# Pulse_Earing_3.net
KiCad netlist of a schematic drawn in EAGLE
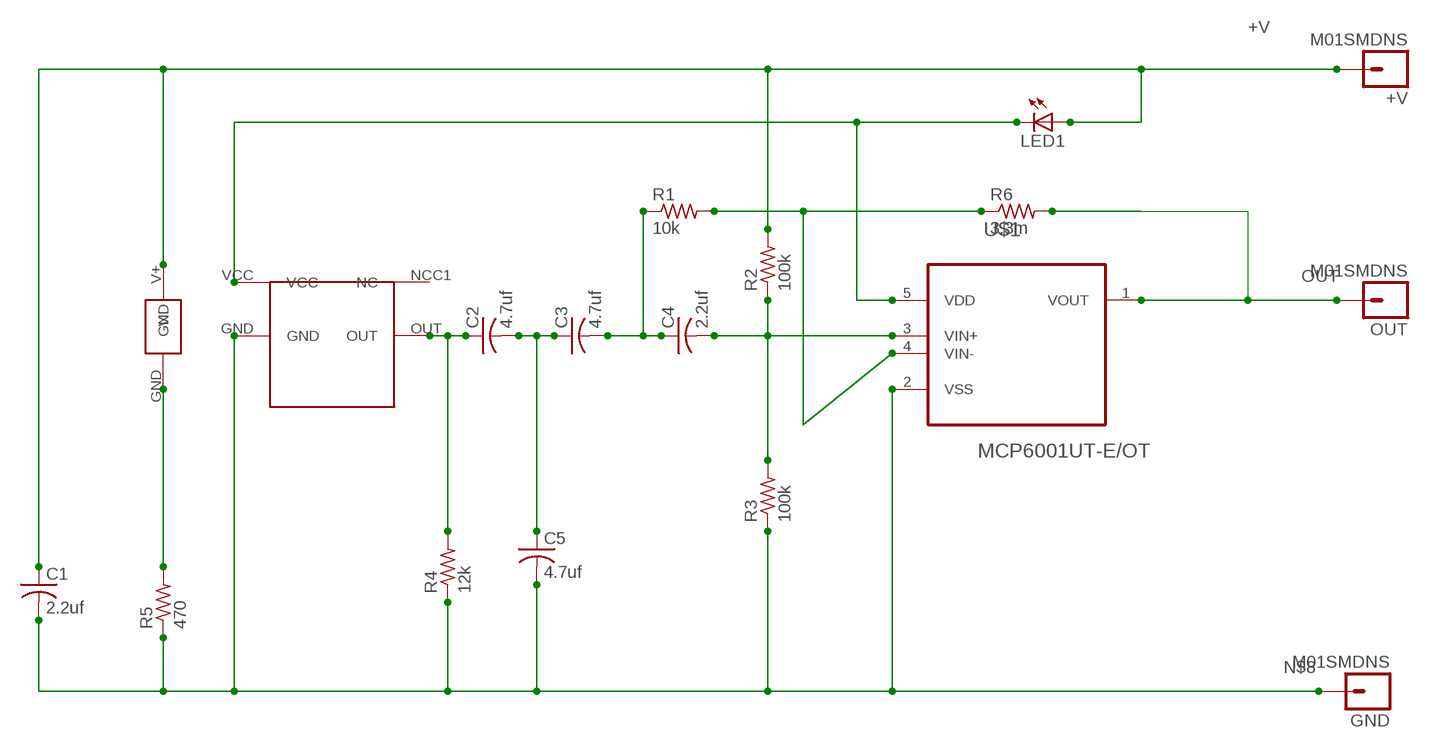
[diagram p0: schematic, sheet 1]

(export (version "E")
  (design (tool "Eeschema 10.0.6"))
  (components
    (comp (ref "+V")
      (value "M01SMDNS")
      (footprint "eagle-import:1X01NS")
      (libsource (lib "eagle-import") (part "M01SMDNS"))
    )
    (comp (ref "C1")
      (value "2.2uf")
      (footprint "eagle-import:C0402")
      (libsource (lib "eagle-import") (part "C-USC0402"))
    )
    (comp (ref "C2")
      (value "4.7uf")
      (footprint "eagle-import:C0402")
      (libsource (lib "eagle-import") (part "C-USC0402"))
    )
    (comp (ref "C3")
      (value "4.7uf")
      (footprint "eagle-import:C0402")
      (libsource (lib "eagle-import") (part "C-USC0402"))
    )
    (comp (ref "C4")
      (value "2.2uf")
      (footprint "eagle-import:C0402")
      (libsource (lib "eagle-import") (part "C-USC0402"))
    )
    (comp (ref "C5")
      (value "4.7uf")
      (footprint "eagle-import:C0402")
      (libsource (lib "eagle-import") (part "C-USC0402"))
    )
    (comp (ref "GND")
      (value "M01SMDNS")
      (footprint "eagle-import:1X01NS")
      (libsource (lib "eagle-import") (part "M01SMDNS"))
    )
    (comp (ref "LED1")
      (value "LEDCHIP-LED0603")
      (footprint "eagle-import:CHIP-LED0603")
      (libsource (lib "eagle-import") (part "LEDCHIP-LED0603"))
    )
    (comp (ref "OUT")
      (value "M01SMDNS")
      (footprint "eagle-import:1X01NS")
      (libsource (lib "eagle-import") (part "M01SMDNS"))
    )
    (comp (ref "R1")
      (value "10k")
      (footprint "eagle-import:R0402")
      (libsource (lib "eagle-import") (part "R-US_R0402"))
    )
    (comp (ref "R2")
      (value "100k")
      (footprint "eagle-import:R0402")
      (libsource (lib "eagle-import") (part "R-US_R0402"))
    )
    (comp (ref "R3")
      (value "100k")
      (footprint "eagle-import:R0402")
      (libsource (lib "eagle-import") (part "R-US_R0402"))
    )
    (comp (ref "R4")
      (value "12k")
      (footprint "eagle-import:R0402")
      (libsource (lib "eagle-import") (part "R-US_R0402"))
    )
    (comp (ref "R5")
      (value "470")
      (footprint "eagle-import:R0402")
      (libsource (lib "eagle-import") (part "R-US_R0402"))
    )
    (comp (ref "R6")
      (value "3.3m")
      (footprint "eagle-import:R0402")
      (libsource (lib "eagle-import") (part "R-US_R0402"))
    )
    (comp (ref "U$1")
      (value "MCP6001UT-E/OT")
      (footprint "eagle-import:SOT95P270X145-5N")
      (libsource (lib "eagle-import") (part "MCP6001UT-E/OT"))
    )
    (comp (ref "U$2")
      (value "APDS9008")
      (footprint "eagle-import:APDS9008")
      (libsource (lib "eagle-import") (part "APDS9008"))
    )
    (comp (ref "U$3")
      (value "KBREVMTNLED")
      (footprint "eagle-import:KBREVMNTLED")
      (libsource (lib "eagle-import") (part "KBREVMTNLED"))
    )
  )
  (nets
    (net (code "1") (name "/+V") (class "Default")
      (node (ref "+V") (pin "1") (pinfunction "1_1") (pintype "passive"))
      (node (ref "C1") (pin "1") (pinfunction "1_1") (pintype "passive"))
      (node (ref "LED1") (pin "A") (pinfunction "A_A") (pintype "passive"))
      (node (ref "R2") (pin "2") (pinfunction "2_2") (pintype "passive"))
      (node (ref "U$3") (pin "V+") (pinfunction "V_V+") (pintype "bidirectional"))
    )
    (net (code "2") (name "/N$8") (class "Default")
      (node (ref "C1") (pin "2") (pinfunction "2_2") (pintype "passive"))
      (node (ref "C5") (pin "2") (pinfunction "2_2") (pintype "passive"))
      (node (ref "GND") (pin "1") (pinfunction "1_1") (pintype "passive"))
      (node (ref "R3") (pin "1") (pinfunction "1_1") (pintype "passive"))
      (node (ref "R4") (pin "1") (pinfunction "1_1") (pintype "passive"))
      (node (ref "R5") (pin "1") (pinfunction "1_1") (pintype "passive"))
      (node (ref "U$1") (pin "2") (pinfunction "VSS_2") (pintype "passive"))
      (node (ref "U$2") (pin "GND") (pinfunction "GND_GND") (pintype "bidirectional"))
    )
    (net (code "3") (name "/OUT") (class "Default")
      (node (ref "OUT") (pin "1") (pinfunction "1_1") (pintype "passive"))
      (node (ref "R6") (pin "2") (pinfunction "2_2") (pintype "passive"))
      (node (ref "U$1") (pin "1") (pinfunction "VOUT_1") (pintype "output"))
    )
    (net (code "4") (name "Net-(C2-Pad1)") (class "Default")
      (node (ref "C2") (pin "1") (pinfunction "1_1") (pintype "passive"))
      (node (ref "R4") (pin "2") (pinfunction "2_2") (pintype "passive"))
      (node (ref "U$2") (pin "OUT") (pinfunction "OUT_OUT") (pintype "bidirectional"))
    )
    (net (code "5") (name "Net-(C2-Pad2)") (class "Default")
      (node (ref "C2") (pin "2") (pinfunction "2_2") (pintype "passive"))
      (node (ref "C3") (pin "1") (pinfunction "1_1") (pintype "passive"))
      (node (ref "C5") (pin "1") (pinfunction "1_1") (pintype "passive"))
    )
    (net (code "6") (name "Net-(C3-Pad2)") (class "Default")
      (node (ref "C3") (pin "2") (pinfunction "2_2") (pintype "passive"))
      (node (ref "C4") (pin "1") (pinfunction "1_1") (pintype "passive"))
      (node (ref "R1") (pin "1") (pinfunction "1_1") (pintype "passive"))
    )
    (net (code "7") (name "Net-(R5-Pad2)") (class "Default")
      (node (ref "R5") (pin "2") (pinfunction "2_2") (pintype "passive"))
      (node (ref "U$3") (pin "GND") (pinfunction "GND_GND") (pintype "bidirectional"))
    )
    (net (code "8") (name "Net-(U$1-VDD)") (class "Default")
      (node (ref "LED1") (pin "C") (pinfunction "C_C") (pintype "passive"))
      (node (ref "U$1") (pin "5") (pinfunction "VDD_5") (pintype "power_in"))
      (node (ref "U$2") (pin "VCC") (pinfunction "VCC_VCC") (pintype "bidirectional"))
    )
    (net (code "9") (name "Net-(U$1-VIN+)") (class "Default")
      (node (ref "C4") (pin "2") (pinfunction "2_2") (pintype "passive"))
      (node (ref "R2") (pin "1") (pinfunction "1_1") (pintype "passive"))
      (node (ref "R3") (pin "2") (pinfunction "2_2") (pintype "passive"))
      (node (ref "U$1") (pin "3") (pinfunction "VIN+_3") (pintype "input"))
    )
    (net (code "10") (name "Net-(U$1-VIN-)") (class "Default")
      (node (ref "R1") (pin "2") (pinfunction "2_2") (pintype "passive"))
      (node (ref "R6") (pin "1") (pinfunction "1_1") (pintype "passive"))
      (node (ref "U$1") (pin "4") (pinfunction "VIN-_4") (pintype "input"))
    )
    (net (code "11") (name "unconnected-(U$2-NC-PadNCC1)") (class "Default")
      (node (ref "U$2") (pin "NCC1") (pinfunction "NC_NCC1") (pintype "bidirectional"))
    )
  )
)
